# Telemetry_AnalogSensors_PTC08_Shifter.net
KiCad netlist of a schematic drawn in Altium Designer
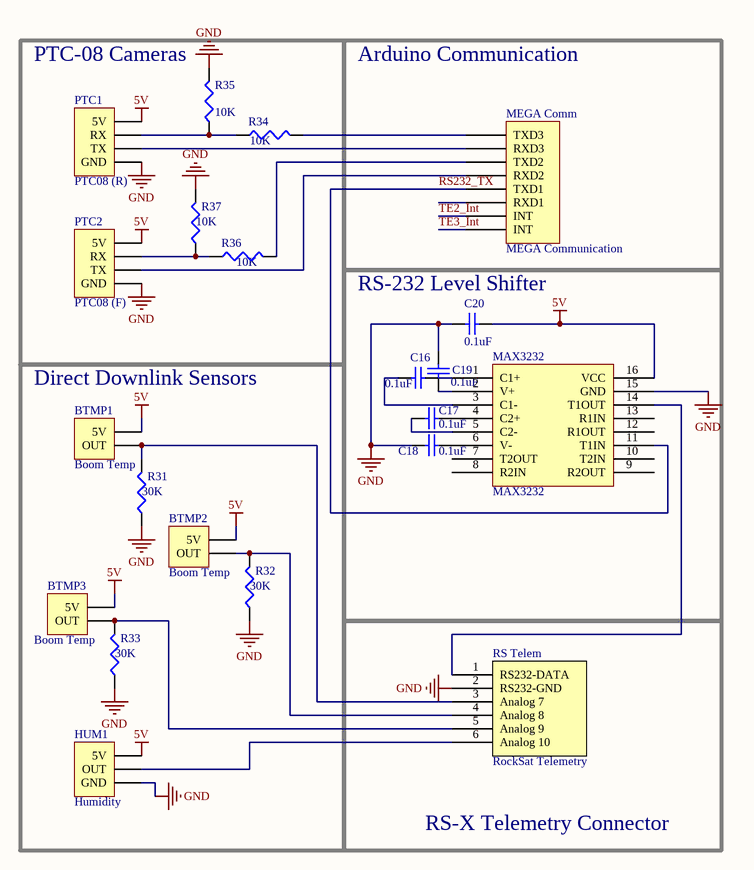
[diagram p0: Telemetry_AnalogSensors_PTC08_Shifter.SchDoc]

(export (version "E")
  (design (tool "Eeschema 10.0.6"))
  (components
    (comp (ref "BTMP1")
      (value "Boom Temp")
      (footprint "HDR1X2")
      (description "Header, 2-Pin")
      (fields (field (name "PUBLISHER") "Altium Limited"))
      (libsource (lib "Miscellaneous Connectors") (part "Header 2"))
    )
    (comp (ref "BTMP2")
      (value "Boom Temp")
      (footprint "HDR1X2")
      (description "Header, 2-Pin")
      (fields (field (name "PUBLISHER") "Altium Limited"))
      (libsource (lib "Miscellaneous Connectors") (part "Header 2"))
    )
    (comp (ref "BTMP3")
      (value "Boom Temp")
      (footprint "HDR1X2")
      (description "Header, 2-Pin")
      (fields (field (name "PUBLISHER") "Altium Limited"))
      (libsource (lib "Miscellaneous Connectors") (part "Header 2"))
    )
    (comp (ref "C16")
      (value "0.1uF")
      (footprint "C1206")
      (description "Capacitor (Semiconductor SIM Model)")
      (fields (field (name "PUBLISHER") "Altium Limited"))
      (libsource (lib "Miscellaneous Devices") (part "Cap Semi"))
    )
    (comp (ref "C17")
      (value "0.1uF")
      (footprint "C1206")
      (description "Capacitor (Semiconductor SIM Model)")
      (fields (field (name "PUBLISHER") "Altium Limited"))
      (libsource (lib "Miscellaneous Devices") (part "Cap Semi"))
    )
    (comp (ref "C18")
      (value "0.1uF")
      (footprint "C1206")
      (description "Capacitor (Semiconductor SIM Model)")
      (fields (field (name "PUBLISHER") "Altium Limited"))
      (libsource (lib "Miscellaneous Devices") (part "Cap Semi"))
    )
    (comp (ref "C19")
      (value "0.1uF")
      (footprint "C1206")
      (description "Capacitor (Semiconductor SIM Model)")
      (fields (field (name "PUBLISHER") "Altium Limited"))
      (libsource (lib "Miscellaneous Devices") (part "Cap Semi"))
    )
    (comp (ref "C20")
      (value "0.1uF")
      (footprint "C1206")
      (description "Capacitor (Semiconductor SIM Model)")
      (fields (field (name "PUBLISHER") "Altium Limited"))
      (libsource (lib "Miscellaneous Devices") (part "Cap Semi"))
    )
    (comp (ref "HUM1")
      (value "Humidity")
      (footprint "HDR1X3")
      (description "Header, 3-Pin")
      (fields (field (name "PUBLISHER") "Altium Limited"))
      (libsource (lib "Miscellaneous Connectors") (part "Header 3"))
    )
    (comp (ref "MAX3232")
      (value "MAX3232")
      (footprint "rs232")
      (libsource (lib "RS232_Better") (part "MAX3232"))
    )
    (comp (ref "MEGA Comm")
      (value "MEGA Communication")
      (footprint "HDR1X8")
      (libsource (lib "Arduino8Header") (part "Component_1"))
    )
    (comp (ref "PTC1")
      (value "PTC08 (R)")
      (footprint "HDR1X4")
      (description "Header, 4-Pin")
      (fields (field (name "PUBLISHER") "Altium Limited"))
      (libsource (lib "Miscellaneous Connectors") (part "Header 4"))
    )
    (comp (ref "PTC2")
      (value "PTC08 (F)")
      (footprint "HDR1X4")
      (description "Header, 4-Pin")
      (fields (field (name "PUBLISHER") "Altium Limited"))
      (libsource (lib "Miscellaneous Connectors") (part "Header 4"))
    )
    (comp (ref "R31")
      (value "30K")
      (footprint "J1-0603")
      (description "Resistor")
      (fields (field (name "PUBLISHER") "Altium Limited"))
      (libsource (lib "Miscellaneous Devices") (part "Res3"))
    )
    (comp (ref "R32")
      (value "30K")
      (footprint "J1-0603")
      (description "Resistor")
      (fields (field (name "PUBLISHER") "Altium Limited"))
      (libsource (lib "Miscellaneous Devices") (part "Res3"))
    )
    (comp (ref "R33")
      (value "30K")
      (footprint "J1-0603")
      (description "Resistor")
      (fields (field (name "PUBLISHER") "Altium Limited"))
      (libsource (lib "Miscellaneous Devices") (part "Res3"))
    )
    (comp (ref "R34")
      (value "10K")
      (footprint "J1-0603")
      (description "Resistor")
      (fields (field (name "PUBLISHER") "Altium Limited"))
      (libsource (lib "Miscellaneous Devices") (part "Res3"))
    )
    (comp (ref "R35")
      (value "10K")
      (footprint "J1-0603")
      (description "Resistor")
      (fields (field (name "PUBLISHER") "Altium Limited"))
      (libsource (lib "Miscellaneous Devices") (part "Res3"))
    )
    (comp (ref "R36")
      (value "10K")
      (footprint "J1-0603")
      (description "Resistor")
      (fields (field (name "PUBLISHER") "Altium Limited"))
      (libsource (lib "Miscellaneous Devices") (part "Res3"))
    )
    (comp (ref "R37")
      (value "10K")
      (footprint "J1-0603")
      (description "Resistor")
      (fields (field (name "PUBLISHER") "Altium Limited"))
      (libsource (lib "Miscellaneous Devices") (part "Res3"))
    )
    (comp (ref "RS Telem")
      (value "RockSat Telemetry")
      (footprint "HDR1X6")
      (libsource (lib "RSX_Telemetry") (part "Component_1"))
    )
  )
  (nets
    (net (code "1") (name "/RS232_TX") (class "Default")
      (node (ref "MAX3232") (pin "11") (pinfunction "T1IN_11") (pintype "passive"))
      (node (ref "MEGA Comm") (pin "5") (pinfunction "TXD1_5") (pintype "passive"))
    )
    (net (code "2") (name "/TE2_Int") (class "Default")
      (node (ref "MEGA Comm") (pin "7") (pinfunction "INT_7") (pintype "passive"))
    )
    (net (code "3") (name "/TE3_Int") (class "Default")
      (node (ref "MEGA Comm") (pin "8") (pinfunction "INT_8") (pintype "passive"))
    )
    (net (code "4") (name "5V") (class "Default")
      (node (ref "BTMP1") (pin "1") (pinfunction "5V_1") (pintype "passive"))
      (node (ref "BTMP2") (pin "1") (pinfunction "5V_1") (pintype "passive"))
      (node (ref "BTMP3") (pin "1") (pinfunction "5V_1") (pintype "passive"))
      (node (ref "C20") (pin "1") (pinfunction "1_1") (pintype "passive"))
      (node (ref "HUM1") (pin "3") (pinfunction "5V_3") (pintype "passive"))
      (node (ref "MAX3232") (pin "16") (pinfunction "VCC_16") (pintype "passive"))
      (node (ref "PTC1") (pin "1") (pinfunction "5V_1") (pintype "passive"))
      (node (ref "PTC2") (pin "1") (pinfunction "5V_1") (pintype "passive"))
    )
    (net (code "5") (name "GND") (class "Default")
      (node (ref "C18") (pin "1") (pinfunction "1_1") (pintype "passive"))
      (node (ref "C19") (pin "2") (pinfunction "2_2") (pintype "passive"))
      (node (ref "C20") (pin "2") (pinfunction "2_2") (pintype "passive"))
      (node (ref "HUM1") (pin "1") (pinfunction "GND_1") (pintype "passive"))
      (node (ref "MAX3232") (pin "15") (pinfunction "GND_15") (pintype "passive"))
      (node (ref "PTC1") (pin "4") (pinfunction "GND_4") (pintype "passive"))
      (node (ref "PTC2") (pin "4") (pinfunction "GND_4") (pintype "passive"))
      (node (ref "R31") (pin "1") (pinfunction "1_1") (pintype "passive"))
      (node (ref "R32") (pin "1") (pinfunction "1_1") (pintype "passive"))
      (node (ref "R33") (pin "1") (pinfunction "1_1") (pintype "passive"))
      (node (ref "R35") (pin "2") (pinfunction "2_2") (pintype "passive"))
      (node (ref "R37") (pin "2") (pinfunction "2_2") (pintype "passive"))
      (node (ref "RS Telem") (pin "2") (pinfunction "RS232-GND_2") (pintype "passive"))
    )
    (net (code "6") (name "Net-(BTMP1-OUT)") (class "Default")
      (node (ref "BTMP1") (pin "2") (pinfunction "OUT_2") (pintype "passive"))
      (node (ref "R31") (pin "2") (pinfunction "2_2") (pintype "passive"))
      (node (ref "RS Telem") (pin "3") (pinfunction "Analog_7_3") (pintype "passive"))
    )
    (net (code "7") (name "Net-(BTMP2-OUT)") (class "Default")
      (node (ref "BTMP2") (pin "2") (pinfunction "OUT_2") (pintype "passive"))
      (node (ref "R32") (pin "2") (pinfunction "2_2") (pintype "passive"))
      (node (ref "RS Telem") (pin "4") (pinfunction "Analog_8_4") (pintype "passive"))
    )
    (net (code "8") (name "Net-(BTMP3-OUT)") (class "Default")
      (node (ref "BTMP3") (pin "2") (pinfunction "OUT_2") (pintype "passive"))
      (node (ref "R33") (pin "2") (pinfunction "2_2") (pintype "passive"))
      (node (ref "RS Telem") (pin "5") (pinfunction "Analog_9_5") (pintype "passive"))
    )
    (net (code "9") (name "Net-(HUM1-OUT)") (class "Default")
      (node (ref "HUM1") (pin "2") (pinfunction "OUT_2") (pintype "passive"))
      (node (ref "RS Telem") (pin "6") (pinfunction "Analog_10_6") (pintype "passive"))
    )
    (net (code "10") (name "Net-(MAX3232-C1+)") (class "Default")
      (node (ref "C16") (pin "1") (pinfunction "1_1") (pintype "passive"))
      (node (ref "MAX3232") (pin "1") (pinfunction "C1+_1") (pintype "passive"))
    )
    (net (code "11") (name "Net-(MAX3232-C1-)") (class "Default")
      (node (ref "C16") (pin "2") (pinfunction "2_2") (pintype "passive"))
      (node (ref "MAX3232") (pin "3") (pinfunction "C1-_3") (pintype "passive"))
    )
    (net (code "12") (name "Net-(MAX3232-C2+)") (class "Default")
      (node (ref "C17") (pin "1") (pinfunction "1_1") (pintype "passive"))
      (node (ref "MAX3232") (pin "4") (pinfunction "C2+_4") (pintype "passive"))
    )
    (net (code "13") (name "Net-(MAX3232-C2-)") (class "Default")
      (node (ref "C17") (pin "2") (pinfunction "2_2") (pintype "passive"))
      (node (ref "MAX3232") (pin "5") (pinfunction "C2-_5") (pintype "passive"))
    )
    (net (code "14") (name "Net-(MAX3232-T1OUT)") (class "Default")
      (node (ref "MAX3232") (pin "14") (pinfunction "T1OUT_14") (pintype "passive"))
      (node (ref "RS Telem") (pin "1") (pinfunction "RS232-DATA_1") (pintype "passive"))
    )
    (net (code "15") (name "Net-(MAX3232-V+)") (class "Default")
      (node (ref "C19") (pin "1") (pinfunction "1_1") (pintype "passive"))
      (node (ref "MAX3232") (pin "2") (pinfunction "V+_2") (pintype "passive"))
    )
    (net (code "16") (name "Net-(MAX3232-V-)") (class "Default")
      (node (ref "C18") (pin "2") (pinfunction "2_2") (pintype "passive"))
      (node (ref "MAX3232") (pin "6") (pinfunction "V-_6") (pintype "passive"))
    )
    (net (code "17") (name "Net-(MEGA Comm-RXD2)") (class "Default")
      (node (ref "MEGA Comm") (pin "4") (pinfunction "RXD2_4") (pintype "passive"))
      (node (ref "PTC2") (pin "3") (pinfunction "TX_3") (pintype "passive"))
    )
    (net (code "18") (name "Net-(MEGA Comm-RXD3)") (class "Default")
      (node (ref "MEGA Comm") (pin "2") (pinfunction "RXD3_2") (pintype "passive"))
      (node (ref "PTC1") (pin "3") (pinfunction "TX_3") (pintype "passive"))
    )
    (net (code "19") (name "Net-(MEGA Comm-TXD2)") (class "Default")
      (node (ref "MEGA Comm") (pin "3") (pinfunction "TXD2_3") (pintype "passive"))
      (node (ref "R36") (pin "2") (pinfunction "2_2") (pintype "passive"))
    )
    (net (code "20") (name "Net-(MEGA Comm-TXD3)") (class "Default")
      (node (ref "MEGA Comm") (pin "1") (pinfunction "TXD3_1") (pintype "passive"))
      (node (ref "R34") (pin "2") (pinfunction "2_2") (pintype "passive"))
    )
    (net (code "21") (name "Net-(PTC1-RX)") (class "Default")
      (node (ref "PTC1") (pin "2") (pinfunction "RX_2") (pintype "passive"))
      (node (ref "R34") (pin "1") (pinfunction "1_1") (pintype "passive"))
      (node (ref "R35") (pin "1") (pinfunction "1_1") (pintype "passive"))
    )
    (net (code "22") (name "Net-(PTC2-RX)") (class "Default")
      (node (ref "PTC2") (pin "2") (pinfunction "RX_2") (pintype "passive"))
      (node (ref "R36") (pin "1") (pinfunction "1_1") (pintype "passive"))
      (node (ref "R37") (pin "1") (pinfunction "1_1") (pintype "passive"))
    )
    (net (code "23") (name "unconnected-(MAX3232-R1IN-Pad13)") (class "Default")
      (node (ref "MAX3232") (pin "13") (pinfunction "R1IN_13") (pintype "passive"))
    )
    (net (code "24") (name "unconnected-(MAX3232-R1OUT-Pad12)") (class "Default")
      (node (ref "MAX3232") (pin "12") (pinfunction "R1OUT_12") (pintype "passive"))
    )
    (net (code "25") (name "unconnected-(MAX3232-R2IN-Pad8)") (class "Default")
      (node (ref "MAX3232") (pin "8") (pinfunction "R2IN_8") (pintype "passive"))
    )
    (net (code "26") (name "unconnected-(MAX3232-R2OUT-Pad9)") (class "Default")
      (node (ref "MAX3232") (pin "9") (pinfunction "R2OUT_9") (pintype "passive"))
    )
    (net (code "27") (name "unconnected-(MAX3232-T2IN-Pad10)") (class "Default")
      (node (ref "MAX3232") (pin "10") (pinfunction "T2IN_10") (pintype "passive"))
    )
    (net (code "28") (name "unconnected-(MAX3232-T2OUT-Pad7)") (class "Default")
      (node (ref "MAX3232") (pin "7") (pinfunction "T2OUT_7") (pintype "passive"))
    )
    (net (code "29") (name "unconnected-(MEGA Comm-RXD1-Pad6)") (class "Default")
      (node (ref "MEGA Comm") (pin "6") (pinfunction "RXD1_6") (pintype "passive"))
    )
  )
)
